# regulator.net
KiCad netlist of a schematic drawn in EAGLE
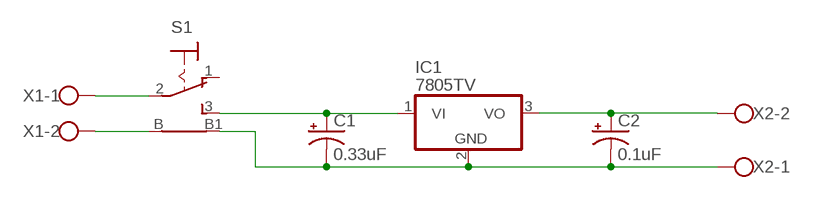
[diagram p0: schematic, sheet 1]

(export (version "E")
  (design (tool "Eeschema 10.0.6"))
  (components
    (comp (ref "C1")
      (value "0.33uF")
      (footprint "eagle-import:E3,5-8")
      (libsource (lib "eagle-import") (part "CPOL-USE3.5-8"))
    )
    (comp (ref "C2")
      (value "0.1uF")
      (footprint "eagle-import:E2-4")
      (libsource (lib "eagle-import") (part "CPOL-USE2-4"))
    )
    (comp (ref "IC1")
      (value "7805TV")
      (footprint "eagle-import:TO220V")
      (libsource (lib "eagle-import") (part "78TV05"))
    )
    (comp (ref "S1")
      (value "9070-1W")
      (footprint "eagle-import:9070-1W")
      (libsource (lib "eagle-import") (part "9070-1W"))
    )
    (comp (ref "X1")
      (value "W237-102")
      (footprint "eagle-import:W237-102")
      (fields (field (name "MPN") "237-102"))
      (libsource (lib "eagle-import") (part "W237-102"))
    )
    (comp (ref "X2")
      (value "W237-102")
      (footprint "eagle-import:W237-102")
      (fields (field (name "MPN") "237-102"))
      (libsource (lib "eagle-import") (part "W237-102"))
    )
  )
  (nets
    (net (code "1") (name "Net-(IC1-GND)") (class "Default")
      (node (ref "C1") (pin "-") (pinfunction "-_-") (pintype "passive"))
      (node (ref "C2") (pin "-") (pinfunction "-_-") (pintype "passive"))
      (node (ref "IC1") (pin "2") (pinfunction "GND_2") (pintype "passive"))
      (node (ref "S1") (pin "B1") (pinfunction "B1_B1") (pintype "passive"))
      (node (ref "X2") (pin "1") (pinfunction "KL_1") (pintype "passive"))
    )
    (net (code "2") (name "Net-(IC1-VI)") (class "Default")
      (node (ref "C1") (pin "+") (pinfunction "+_+") (pintype "passive"))
      (node (ref "IC1") (pin "1") (pinfunction "VI_1") (pintype "input"))
      (node (ref "S1") (pin "3") (pinfunction "S_3") (pintype "passive"))
    )
    (net (code "3") (name "Net-(IC1-VO)") (class "Default")
      (node (ref "C2") (pin "+") (pinfunction "+_+") (pintype "passive"))
      (node (ref "IC1") (pin "3") (pinfunction "VO_3") (pintype "passive"))
      (node (ref "X2") (pin "2") (pinfunction "KL_2") (pintype "passive"))
    )
    (net (code "4") (name "Net-(S1-P)") (class "Default")
      (node (ref "S1") (pin "2") (pinfunction "P_2") (pintype "passive"))
      (node (ref "X1") (pin "1") (pinfunction "KL_1") (pintype "passive"))
    )
    (net (code "5") (name "Net-(X1B-KL)") (class "Default")
      (node (ref "S1") (pin "B") (pinfunction "B_B") (pintype "passive"))
      (node (ref "X1") (pin "2") (pinfunction "KL_2") (pintype "passive"))
    )
    (net (code "6") (name "unconnected-(S1-O-Pad1)") (class "Default")
      (node (ref "S1") (pin "1") (pinfunction "O_1") (pintype "passive"))
    )
  )
)
